# Schematic_ACSI2STM_Compact_EasyEda.net
KiCad netlist of a schematic drawn in EasyEDA
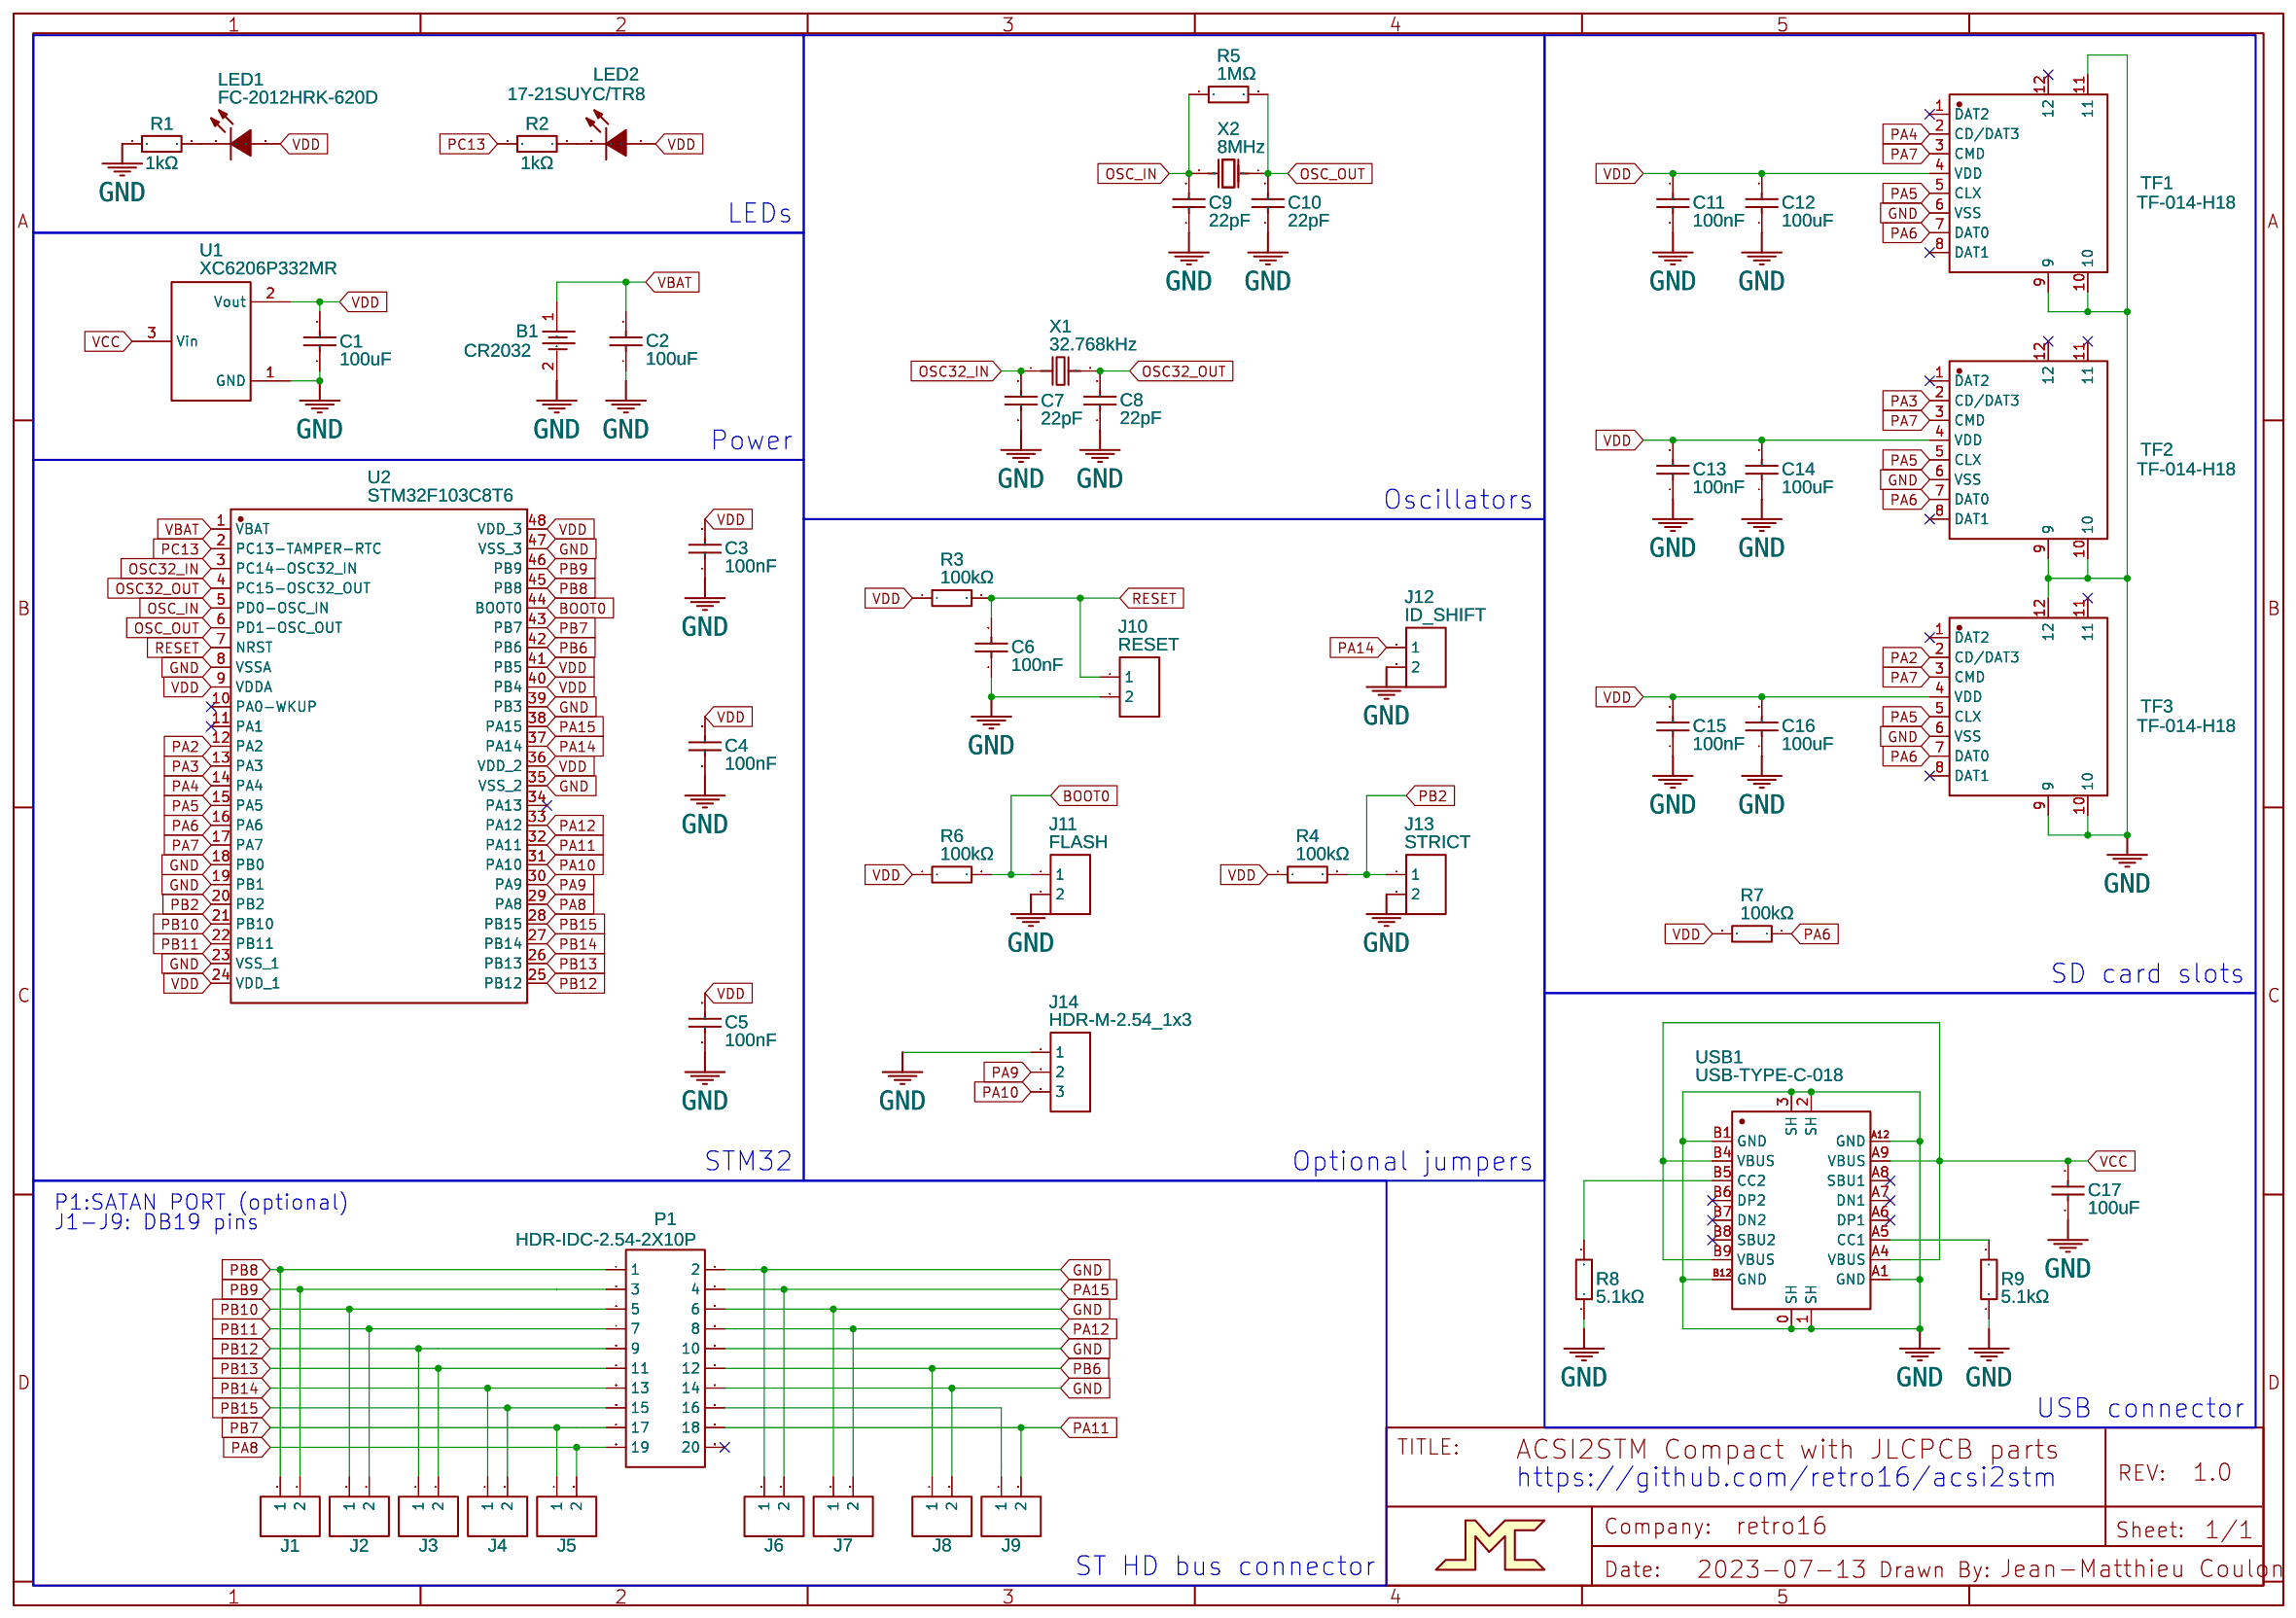
[diagram p0: schematic sheet]

(export (version "E")
  (design (tool "Eeschema 10.0.6"))
  (components
    (comp (ref "B1")
      (value "CR2032")
      (fields
        (field (name "BOM_Manufacturer Part") "CR2032-BS-6-1")
        (field (name "BOM_Supplier Part") "C70377")
      )
      (libsource (lib "") (part "CR2032-BS-6-1"))
    )
    (comp (ref "C1")
      (value "100uF")
      (fields
        (field (name "BOM_Manufacturer Part") "CL31A107MQHNNNE")
        (field (name "BOM_Supplier Part") "C15008")
      )
      (libsource (lib "") (part "CL31A107MQHNNNE"))
    )
    (comp (ref "C2")
      (value "100uF")
      (fields
        (field (name "BOM_Manufacturer Part") "CL31A107MQHNNNE")
        (field (name "BOM_Supplier Part") "C15008")
      )
      (libsource (lib "") (part "CL31A107MQHNNNE"))
    )
    (comp (ref "C3")
      (value "100nF")
      (fields
        (field (name "BOM_Manufacturer Part") "CL05B104KO5NNNC")
        (field (name "BOM_Supplier Part") "C1525")
      )
      (libsource (lib "") (part "CL05B104KO5NNNC"))
    )
    (comp (ref "C4")
      (value "100nF")
      (fields
        (field (name "BOM_Manufacturer Part") "CL05B104KO5NNNC")
        (field (name "BOM_Supplier Part") "C1525")
      )
      (libsource (lib "") (part "CL05B104KO5NNNC"))
    )
    (comp (ref "C5")
      (value "100nF")
      (fields
        (field (name "BOM_Manufacturer Part") "CL05B104KO5NNNC")
        (field (name "BOM_Supplier Part") "C1525")
      )
      (libsource (lib "") (part "CL05B104KO5NNNC"))
    )
    (comp (ref "C6")
      (value "100nF")
      (fields
        (field (name "BOM_Manufacturer Part") "CL05B104KO5NNNC")
        (field (name "BOM_Supplier Part") "C1525")
      )
      (libsource (lib "") (part "CL05B104KO5NNNC"))
    )
    (comp (ref "C7")
      (value "22pF")
      (fields
        (field (name "BOM_Manufacturer Part") "0402CG220J500NT")
        (field (name "BOM_Supplier Part") "C1555")
      )
      (libsource (lib "") (part "0402CG220J500NT"))
    )
    (comp (ref "C8")
      (value "22pF")
      (fields
        (field (name "BOM_Manufacturer Part") "0402CG220J500NT")
        (field (name "BOM_Supplier Part") "C1555")
      )
      (libsource (lib "") (part "0402CG220J500NT"))
    )
    (comp (ref "C9")
      (value "22pF")
      (fields
        (field (name "BOM_Manufacturer Part") "0402CG220J500NT")
        (field (name "BOM_Supplier Part") "C1555")
      )
      (libsource (lib "") (part "0402CG220J500NT"))
    )
    (comp (ref "C10")
      (value "22pF")
      (fields
        (field (name "BOM_Manufacturer Part") "0402CG220J500NT")
        (field (name "BOM_Supplier Part") "C1555")
      )
      (libsource (lib "") (part "0402CG220J500NT"))
    )
    (comp (ref "C11")
      (value "100nF")
      (fields
        (field (name "BOM_Manufacturer Part") "CL05B104KO5NNNC")
        (field (name "BOM_Supplier Part") "C1525")
      )
      (libsource (lib "") (part "CL05B104KO5NNNC"))
    )
    (comp (ref "C12")
      (value "100uF")
      (fields
        (field (name "BOM_Manufacturer Part") "CL31A107MQHNNNE")
        (field (name "BOM_Supplier Part") "C15008")
      )
      (libsource (lib "") (part "CL31A107MQHNNNE"))
    )
    (comp (ref "C13")
      (value "100nF")
      (fields
        (field (name "BOM_Manufacturer Part") "CL05B104KO5NNNC")
        (field (name "BOM_Supplier Part") "C1525")
      )
      (libsource (lib "") (part "CL05B104KO5NNNC"))
    )
    (comp (ref "C14")
      (value "100uF")
      (fields
        (field (name "BOM_Manufacturer Part") "CL31A107MQHNNNE")
        (field (name "BOM_Supplier Part") "C15008")
      )
      (libsource (lib "") (part "CL31A107MQHNNNE"))
    )
    (comp (ref "C15")
      (value "100nF")
      (fields
        (field (name "BOM_Manufacturer Part") "CL05B104KO5NNNC")
        (field (name "BOM_Supplier Part") "C1525")
      )
      (libsource (lib "") (part "CL05B104KO5NNNC"))
    )
    (comp (ref "C16")
      (value "100uF")
      (fields
        (field (name "BOM_Manufacturer Part") "CL31A107MQHNNNE")
        (field (name "BOM_Supplier Part") "C15008")
      )
      (libsource (lib "") (part "CL31A107MQHNNNE"))
    )
    (comp (ref "C17")
      (value "100uF")
      (fields
        (field (name "BOM_Manufacturer Part") "CL31A107MQHNNNE")
        (field (name "BOM_Supplier Part") "C15008")
      )
      (libsource (lib "") (part "CL31A107MQHNNNE"))
    )
    (comp (ref "J1")
      (value "HDR-M-2.54_1x2")
      (fields (field (name "BOM_Supplier Part") "C124375"))
      (libsource (lib "") (part "HDR-M-2.54_1x2"))
    )
    (comp (ref "J2")
      (value "HDR-M-2.54_1x2")
      (fields (field (name "BOM_Supplier Part") "C124375"))
      (libsource (lib "") (part "HDR-M-2.54_1x2"))
    )
    (comp (ref "J3")
      (value "HDR-M-2.54_1x2")
      (fields (field (name "BOM_Supplier Part") "C124375"))
      (libsource (lib "") (part "HDR-M-2.54_1x2"))
    )
    (comp (ref "J4")
      (value "HDR-M-2.54_1x2")
      (fields (field (name "BOM_Supplier Part") "C124375"))
      (libsource (lib "") (part "HDR-M-2.54_1x2"))
    )
    (comp (ref "J5")
      (value "HDR-M-2.54_1x2")
      (fields (field (name "BOM_Supplier Part") "C124375"))
      (libsource (lib "") (part "HDR-M-2.54_1x2"))
    )
    (comp (ref "J6")
      (value "HDR-M-2.54_1x2")
      (fields (field (name "BOM_Supplier Part") "C124375"))
      (libsource (lib "") (part "HDR-M-2.54_1x2"))
    )
    (comp (ref "J7")
      (value "HDR-M-2.54_1x2")
      (fields (field (name "BOM_Supplier Part") "C124375"))
      (libsource (lib "") (part "HDR-M-2.54_1x2"))
    )
    (comp (ref "J8")
      (value "HDR-M-2.54_1x2")
      (fields (field (name "BOM_Supplier Part") "C124375"))
      (libsource (lib "") (part "HDR-M-2.54_1x2"))
    )
    (comp (ref "J9")
      (value "HDR-M-2.54_1x2")
      (fields (field (name "BOM_Supplier Part") "C124375"))
      (libsource (lib "") (part "HDR-M-2.54_1x2"))
    )
    (comp (ref "J10")
      (value "RESET")
      (fields (field (name "BOM_Supplier Part") "C124375"))
      (libsource (lib "") (part "HDR-M-2.54_1x2_1"))
    )
    (comp (ref "J11")
      (value "FLASH")
      (fields (field (name "BOM_Supplier Part") "C124375"))
      (libsource (lib "") (part "HDR-M-2.54_1x2_1"))
    )
    (comp (ref "J12")
      (value "ID_SHIFT")
      (fields (field (name "BOM_Supplier Part") "C124375"))
      (libsource (lib "") (part "HDR-M-2.54_1x2_1"))
    )
    (comp (ref "J13")
      (value "STRICT")
      (fields (field (name "BOM_Supplier Part") "C124375"))
      (libsource (lib "") (part "HDR-M-2.54_1x2_1"))
    )
    (comp (ref "J14")
      (value "HDR-M-2.54_1x3")
      (fields (field (name "BOM_Supplier Part") "C180248"))
      (libsource (lib "") (part "HDR-M-2.54_1x3"))
    )
    (comp (ref "LED1")
      (value "FC-2012HRK-620D")
      (fields (field (name "BOM_Manufacturer Part") "NCD0805R1") (field (name "BOM_Supplier Part") "C84256"))
      (libsource (lib "") (part "FC-2012HRK-620D"))
    )
    (comp (ref "LED2")
      (value "17-21SUYC/TR8")
      (fields (field (name "BOM_Manufacturer Part") "KT-0805黄灯") (field (name "BOM_Supplier Part") "C2296"))
      (libsource (lib "") (part "17-21SUYC/TR8"))
    )
    (comp (ref "P1")
      (value "HDR-IDC-2.54-2X10P")
      (fields
        (field (name "BOM_Manufacturer Part") "IDC Box 2.54mm 2X10P　Straight")
        (field (name "BOM_Supplier Part") "C3405")
      )
      (libsource (lib "") (part "HDR-IDC-2.54-2X10P"))
    )
    (comp (ref "R1")
      (value "1kΩ")
      (fields
        (field (name "BOM_Manufacturer Part") "0402WGF1001TCE")
        (field (name "BOM_Supplier Part") "C11702")
      )
      (libsource (lib "") (part "0402WGF1001TCE"))
    )
    (comp (ref "R2")
      (value "1kΩ")
      (fields
        (field (name "BOM_Manufacturer Part") "0402WGF1001TCE")
        (field (name "BOM_Supplier Part") "C11702")
      )
      (libsource (lib "") (part "0402WGF1001TCE"))
    )
    (comp (ref "R3")
      (value "100kΩ")
      (fields
        (field (name "BOM_Manufacturer Part") "0402WGF1003TCE")
        (field (name "BOM_Supplier Part") "C25741")
      )
      (libsource (lib "") (part "0402WGF1003TCE"))
    )
    (comp (ref "R4")
      (value "100kΩ")
      (fields
        (field (name "BOM_Manufacturer Part") "0402WGF1003TCE")
        (field (name "BOM_Supplier Part") "C25741")
      )
      (libsource (lib "") (part "0402WGF1003TCE"))
    )
    (comp (ref "R5")
      (value "1MΩ")
      (fields
        (field (name "BOM_Manufacturer Part") "0402WGF1004TCE")
        (field (name "BOM_Supplier Part") "C26083")
      )
      (libsource (lib "") (part "0402WGF1004TCE"))
    )
    (comp (ref "R6")
      (value "100kΩ")
      (fields
        (field (name "BOM_Manufacturer Part") "0402WGF1003TCE")
        (field (name "BOM_Supplier Part") "C25741")
      )
      (libsource (lib "") (part "0402WGF1003TCE"))
    )
    (comp (ref "R7")
      (value "100kΩ")
      (fields
        (field (name "BOM_Manufacturer Part") "0402WGF1003TCE")
        (field (name "BOM_Supplier Part") "C25741")
      )
      (libsource (lib "") (part "0402WGF1003TCE_1"))
    )
    (comp (ref "R8")
      (value "5.1kΩ")
      (fields
        (field (name "BOM_Manufacturer Part") "0402WGF5101TCE")
        (field (name "BOM_Supplier Part") "C25905")
      )
      (libsource (lib "") (part "0402WGF5101TCE"))
    )
    (comp (ref "R9")
      (value "5.1kΩ")
      (fields
        (field (name "BOM_Manufacturer Part") "0402WGF5101TCE")
        (field (name "BOM_Supplier Part") "C25905")
      )
      (libsource (lib "") (part "0402WGF5101TCE"))
    )
    (comp (ref "TF1")
      (value "TF-014-H18")
      (fields (field (name "BOM_Supplier Part") "C410349"))
      (libsource (lib "") (part "TF-014-H18"))
    )
    (comp (ref "TF2")
      (value "TF-014-H18")
      (fields (field (name "BOM_Supplier Part") "C410349"))
      (libsource (lib "") (part "TF-014-H18"))
    )
    (comp (ref "TF3")
      (value "TF-014-H18")
      (fields (field (name "BOM_Supplier Part") "C410349"))
      (libsource (lib "") (part "TF-014-H18"))
    )
    (comp (ref "U1")
      (value "XC6206P332MR")
      (fields (field (name "BOM_Supplier Part") "C5446"))
      (libsource (lib "") (part "XC6206P332MR"))
    )
    (comp (ref "U2")
      (value "STM32F103C8T6")
      (fields (field (name "BOM_Supplier Part") "C8734"))
      (libsource (lib "") (part "STM32F103C8T6"))
    )
    (comp (ref "U3") (value "JMC_LOGO") (libsource (lib "") (part "JMC_LOGO")))
    (comp (ref "USB1")
      (value "USB-TYPE-C-018")
      (fields (field (name "BOM_Supplier Part") "C2927038"))
      (libsource (lib "") (part "USB-TYPE-C-018"))
    )
    (comp (ref "X1")
      (value "32.768kHz")
      (fields
        (field (name "BOM_Manufacturer Part") "Q13FC1350000400")
        (field (name "BOM_Supplier Part") "C32346")
      )
      (libsource (lib "") (part "Q13FC1350000400"))
    )
    (comp (ref "X2")
      (value "8MHz")
      (fields
        (field (name "BOM_Manufacturer Part") "X49SM8MSD2SC")
        (field (name "BOM_Supplier Part") "C12674")
      )
      (libsource (lib "") (part "X49SM8MSD2SC"))
    )
  )
  (nets
    (net (code "1") (name "BOOT0") (class "Default")
      (node (ref "J11") (pin "1") (pinfunction "1_1") (pintype "unspecified"))
      (node (ref "R6") (pin "2") (pinfunction "2_2") (pintype "input"))
      (node (ref "U2") (pin "44") (pinfunction "BOOT0_44") (pintype "unspecified"))
    )
    (net (code "2") (name "GND") (class "Default")
      (node (ref "B1") (pin "2") (pinfunction "2_2") (pintype "input"))
      (node (ref "C1") (pin "1") (pinfunction "1_1") (pintype "input"))
      (node (ref "C10") (pin "1") (pinfunction "1_1") (pintype "input"))
      (node (ref "C11") (pin "1") (pinfunction "1_1") (pintype "input"))
      (node (ref "C12") (pin "1") (pinfunction "1_1") (pintype "input"))
      (node (ref "C13") (pin "1") (pinfunction "1_1") (pintype "input"))
      (node (ref "C14") (pin "1") (pinfunction "1_1") (pintype "input"))
      (node (ref "C15") (pin "1") (pinfunction "1_1") (pintype "input"))
      (node (ref "C16") (pin "1") (pinfunction "1_1") (pintype "input"))
      (node (ref "C17") (pin "1") (pinfunction "1_1") (pintype "input"))
      (node (ref "C2") (pin "1") (pinfunction "1_1") (pintype "input"))
      (node (ref "C3") (pin "1") (pinfunction "1_1") (pintype "input"))
      (node (ref "C4") (pin "1") (pinfunction "1_1") (pintype "input"))
      (node (ref "C5") (pin "1") (pinfunction "1_1") (pintype "input"))
      (node (ref "C6") (pin "1") (pinfunction "1_1") (pintype "input"))
      (node (ref "C7") (pin "1") (pinfunction "1_1") (pintype "input"))
      (node (ref "C8") (pin "1") (pinfunction "1_1") (pintype "input"))
      (node (ref "C9") (pin "1") (pinfunction "1_1") (pintype "input"))
      (node (ref "J10") (pin "2") (pinfunction "2_2") (pintype "unspecified"))
      (node (ref "J11") (pin "2") (pinfunction "2_2") (pintype "unspecified"))
      (node (ref "J12") (pin "2") (pinfunction "2_2") (pintype "unspecified"))
      (node (ref "J13") (pin "2") (pinfunction "2_2") (pintype "unspecified"))
      (node (ref "J14") (pin "1") (pinfunction "1_1") (pintype "input"))
      (node (ref "J6") (pin "1") (pinfunction "1_1") (pintype "unspecified"))
      (node (ref "J7") (pin "1") (pinfunction "1_1") (pintype "unspecified"))
      (node (ref "J8") (pin "2") (pinfunction "2_2") (pintype "unspecified"))
      (node (ref "P1") (pin "10") (pinfunction "10_10") (pintype "unspecified"))
      (node (ref "P1") (pin "14") (pinfunction "14_14") (pintype "unspecified"))
      (node (ref "P1") (pin "2") (pinfunction "2_2") (pintype "unspecified"))
      (node (ref "P1") (pin "6") (pinfunction "6_6") (pintype "unspecified"))
      (node (ref "R1") (pin "1") (pinfunction "1_1") (pintype "input"))
      (node (ref "R8") (pin "1") (pinfunction "1_1") (pintype "input"))
      (node (ref "R9") (pin "1") (pinfunction "1_1") (pintype "input"))
      (node (ref "TF1") (pin "10") (pinfunction "10_10") (pintype "unspecified"))
      (node (ref "TF1") (pin "11") (pinfunction "11_11") (pintype "unspecified"))
      (node (ref "TF1") (pin "6") (pinfunction "VSS_6") (pintype "unspecified"))
      (node (ref "TF1") (pin "9") (pinfunction "9_9") (pintype "unspecified"))
      (node (ref "TF2") (pin "10") (pinfunction "10_10") (pintype "unspecified"))
      (node (ref "TF2") (pin "6") (pinfunction "VSS_6") (pintype "unspecified"))
      (node (ref "TF2") (pin "9") (pinfunction "9_9") (pintype "unspecified"))
      (node (ref "TF3") (pin "10") (pinfunction "10_10") (pintype "unspecified"))
      (node (ref "TF3") (pin "12") (pinfunction "12_12") (pintype "unspecified"))
      (node (ref "TF3") (pin "6") (pinfunction "VSS_6") (pintype "unspecified"))
      (node (ref "TF3") (pin "9") (pinfunction "9_9") (pintype "unspecified"))
      (node (ref "U1") (pin "1") (pinfunction "GND_1") (pintype "unspecified"))
      (node (ref "U2") (pin "18") (pinfunction "PB0_18") (pintype "unspecified"))
      (node (ref "U2") (pin "19") (pinfunction "PB1_19") (pintype "unspecified"))
      (node (ref "U2") (pin "23") (pinfunction "VSS_1_23") (pintype "unspecified"))
      (node (ref "U2") (pin "35") (pinfunction "VSS_2_35") (pintype "unspecified"))
      (node (ref "U2") (pin "39") (pinfunction "PB3_39") (pintype "unspecified"))
      (node (ref "U2") (pin "47") (pinfunction "VSS_3_47") (pintype "unspecified"))
      (node (ref "U2") (pin "8") (pinfunction "VSSA_8") (pintype "unspecified"))
      (node (ref "USB1") (pin "0") (pinfunction "SH_0") (pintype "unspecified"))
      (node (ref "USB1") (pin "1") (pinfunction "SH_1") (pintype "unspecified"))
      (node (ref "USB1") (pin "2") (pinfunction "SH_2") (pintype "unspecified"))
      (node (ref "USB1") (pin "3") (pinfunction "SH_3") (pintype "unspecified"))
      (node (ref "USB1") (pin "A1") (pinfunction "GND_A1") (pintype "unspecified"))
      (node (ref "USB1") (pin "A12") (pinfunction "GND_A12") (pintype "unspecified"))
      (node (ref "USB1") (pin "B1") (pinfunction "GND_B1") (pintype "unspecified"))
      (node (ref "USB1") (pin "B12") (pinfunction "GND_B12") (pintype "unspecified"))
    )
    (net (code "3") (name "Net-(J9-Pad1)") (class "Default")
      (node (ref "J9") (pin "1") (pinfunction "1_1") (pintype "unspecified"))
      (node (ref "P1") (pin "16") (pinfunction "16_16") (pintype "unspecified"))
    )
    (net (code "4") (name "Net-(LED1--)") (class "Default")
      (node (ref "LED1") (pin "1") (pinfunction "-_1") (pintype "unspecified"))
      (node (ref "R1") (pin "2") (pinfunction "2_2") (pintype "input"))
    )
    (net (code "5") (name "Net-(LED2--)") (class "Default")
      (node (ref "LED2") (pin "2") (pinfunction "-_2") (pintype "unspecified"))
      (node (ref "R2") (pin "2") (pinfunction "2_2") (pintype "input"))
    )
    (net (code "6") (name "Net-(USB1-CC1)") (class "Default")
      (node (ref "R9") (pin "2") (pinfunction "2_2") (pintype "input"))
      (node (ref "USB1") (pin "A5") (pinfunction "CC1_A5") (pintype "unspecified"))
    )
    (net (code "7") (name "Net-(USB1-CC2)") (class "Default")
      (node (ref "R8") (pin "2") (pinfunction "2_2") (pintype "input"))
      (node (ref "USB1") (pin "B5") (pinfunction "CC2_B5") (pintype "unspecified"))
    )
    (net (code "8") (name "OSC32_IN") (class "Default")
      (node (ref "C7") (pin "2") (pinfunction "2_2") (pintype "input"))
      (node (ref "U2") (pin "3") (pinfunction "PC14-OSC32_IN_3") (pintype "unspecified"))
      (node (ref "X1") (pin "1") (pinfunction "1_1") (pintype "unspecified"))
    )
    (net (code "9") (name "OSC32_OUT") (class "Default")
      (node (ref "C8") (pin "2") (pinfunction "2_2") (pintype "input"))
      (node (ref "U2") (pin "4") (pinfunction "PC15-OSC32_OUT_4") (pintype "unspecified"))
      (node (ref "X1") (pin "2") (pinfunction "2_2") (pintype "unspecified"))
    )
    (net (code "10") (name "OSC_IN") (class "Default")
      (node (ref "C9") (pin "2") (pinfunction "2_2") (pintype "input"))
      (node (ref "R5") (pin "1") (pinfunction "1_1") (pintype "input"))
      (node (ref "U2") (pin "5") (pinfunction "PD0-OSC_IN_5") (pintype "unspecified"))
      (node (ref "X2") (pin "2") (pinfunction "OSC2_2") (pintype "input"))
    )
    (net (code "11") (name "OSC_OUT") (class "Default")
      (node (ref "C10") (pin "2") (pinfunction "2_2") (pintype "input"))
      (node (ref "R5") (pin "2") (pinfunction "2_2") (pintype "input"))
      (node (ref "U2") (pin "6") (pinfunction "PD1-OSC_OUT_6") (pintype "unspecified"))
      (node (ref "X2") (pin "1") (pinfunction "OSC1_1") (pintype "input"))
    )
    (net (code "12") (name "PA2") (class "Default")
      (node (ref "TF3") (pin "2") (pinfunction "CD/DAT3_2") (pintype "unspecified"))
      (node (ref "U2") (pin "12") (pinfunction "PA2_12") (pintype "unspecified"))
    )
    (net (code "13") (name "PA3") (class "Default")
      (node (ref "TF2") (pin "2") (pinfunction "CD/DAT3_2") (pintype "unspecified"))
      (node (ref "U2") (pin "13") (pinfunction "PA3_13") (pintype "unspecified"))
    )
    (net (code "14") (name "PA4") (class "Default")
      (node (ref "TF1") (pin "2") (pinfunction "CD/DAT3_2") (pintype "unspecified"))
      (node (ref "U2") (pin "14") (pinfunction "PA4_14") (pintype "unspecified"))
    )
    (net (code "15") (name "PA5") (class "Default")
      (node (ref "TF1") (pin "5") (pinfunction "CLX_5") (pintype "unspecified"))
      (node (ref "TF2") (pin "5") (pinfunction "CLX_5") (pintype "unspecified"))
      (node (ref "TF3") (pin "5") (pinfunction "CLX_5") (pintype "unspecified"))
      (node (ref "U2") (pin "15") (pinfunction "PA5_15") (pintype "unspecified"))
    )
    (net (code "16") (name "PA6") (class "Default")
      (node (ref "R7") (pin "1") (pinfunction "1_1") (pintype "input"))
      (node (ref "TF1") (pin "7") (pinfunction "DAT0_7") (pintype "unspecified"))
      (node (ref "TF2") (pin "7") (pinfunction "DAT0_7") (pintype "unspecified"))
      (node (ref "TF3") (pin "7") (pinfunction "DAT0_7") (pintype "unspecified"))
      (node (ref "U2") (pin "16") (pinfunction "PA6_16") (pintype "unspecified"))
    )
    (net (code "17") (name "PA7") (class "Default")
      (node (ref "TF1") (pin "3") (pinfunction "CMD_3") (pintype "unspecified"))
      (node (ref "TF2") (pin "3") (pinfunction "CMD_3") (pintype "unspecified"))
      (node (ref "TF3") (pin "3") (pinfunction "CMD_3") (pintype "unspecified"))
      (node (ref "U2") (pin "17") (pinfunction "PA7_17") (pintype "unspecified"))
    )
    (net (code "18") (name "PA8") (class "Default")
      (node (ref "J5") (pin "2") (pinfunction "2_2") (pintype "unspecified"))
      (node (ref "P1") (pin "19") (pinfunction "19_19") (pintype "unspecified"))
      (node (ref "U2") (pin "29") (pinfunction "PA8_29") (pintype "unspecified"))
    )
    (net (code "19") (name "PA9") (class "Default")
      (node (ref "J14") (pin "2") (pinfunction "2_2") (pintype "input"))
      (node (ref "U2") (pin "30") (pinfunction "PA9_30") (pintype "unspecified"))
    )
    (net (code "20") (name "PA10") (class "Default")
      (node (ref "J14") (pin "3") (pinfunction "3_3") (pintype "input"))
      (node (ref "U2") (pin "31") (pinfunction "PA10_31") (pintype "unspecified"))
    )
    (net (code "21") (name "PA11") (class "Default")
      (node (ref "J9") (pin "2") (pinfunction "2_2") (pintype "unspecified"))
      (node (ref "P1") (pin "18") (pinfunction "18_18") (pintype "unspecified"))
      (node (ref "U2") (pin "32") (pinfunction "PA11_32") (pintype "unspecified"))
    )
    (net (code "22") (name "PA12") (class "Default")
      (node (ref "J7") (pin "2") (pinfunction "2_2") (pintype "unspecified"))
      (node (ref "P1") (pin "8") (pinfunction "8_8") (pintype "unspecified"))
      (node (ref "U2") (pin "33") (pinfunction "PA12_33") (pintype "unspecified"))
    )
    (net (code "23") (name "PA14") (class "Default")
      (node (ref "J12") (pin "1") (pinfunction "1_1") (pintype "unspecified"))
      (node (ref "U2") (pin "37") (pinfunction "PA14_37") (pintype "unspecified"))
    )
    (net (code "24") (name "PA15") (class "Default")
      (node (ref "J6") (pin "2") (pinfunction "2_2") (pintype "unspecified"))
      (node (ref "P1") (pin "4") (pinfunction "4_4") (pintype "unspecified"))
      (node (ref "U2") (pin "38") (pinfunction "PA15_38") (pintype "unspecified"))
    )
    (net (code "25") (name "PB2") (class "Default")
      (node (ref "J13") (pin "1") (pinfunction "1_1") (pintype "unspecified"))
      (node (ref "R4") (pin "2") (pinfunction "2_2") (pintype "input"))
      (node (ref "U2") (pin "20") (pinfunction "PB2_20") (pintype "unspecified"))
    )
    (net (code "26") (name "PB6") (class "Default")
      (node (ref "J8") (pin "1") (pinfunction "1_1") (pintype "unspecified"))
      (node (ref "P1") (pin "12") (pinfunction "12_12") (pintype "unspecified"))
      (node (ref "U2") (pin "42") (pinfunction "PB6_42") (pintype "unspecified"))
    )
    (net (code "27") (name "PB7") (class "Default")
      (node (ref "J5") (pin "1") (pinfunction "1_1") (pintype "unspecified"))
      (node (ref "P1") (pin "17") (pinfunction "17_17") (pintype "unspecified"))
      (node (ref "U2") (pin "43") (pinfunction "PB7_43") (pintype "unspecified"))
    )
    (net (code "28") (name "PB8") (class "Default")
      (node (ref "J1") (pin "1") (pinfunction "1_1") (pintype "unspecified"))
      (node (ref "P1") (pin "1") (pinfunction "1_1") (pintype "unspecified"))
      (node (ref "U2") (pin "45") (pinfunction "PB8_45") (pintype "unspecified"))
    )
    (net (code "29") (name "PB9") (class "Default")
      (node (ref "J1") (pin "2") (pinfunction "2_2") (pintype "unspecified"))
      (node (ref "P1") (pin "3") (pinfunction "3_3") (pintype "unspecified"))
      (node (ref "U2") (pin "46") (pinfunction "PB9_46") (pintype "unspecified"))
    )
    (net (code "30") (name "PB10") (class "Default")
      (node (ref "J2") (pin "1") (pinfunction "1_1") (pintype "unspecified"))
      (node (ref "P1") (pin "5") (pinfunction "5_5") (pintype "unspecified"))
      (node (ref "U2") (pin "21") (pinfunction "PB10_21") (pintype "unspecified"))
    )
    (net (code "31") (name "PB11") (class "Default")
      (node (ref "J2") (pin "2") (pinfunction "2_2") (pintype "unspecified"))
      (node (ref "P1") (pin "7") (pinfunction "7_7") (pintype "unspecified"))
      (node (ref "U2") (pin "22") (pinfunction "PB11_22") (pintype "unspecified"))
    )
    (net (code "32") (name "PB12") (class "Default")
      (node (ref "J3") (pin "1") (pinfunction "1_1") (pintype "unspecified"))
      (node (ref "P1") (pin "9") (pinfunction "9_9") (pintype "unspecified"))
      (node (ref "U2") (pin "25") (pinfunction "PB12_25") (pintype "unspecified"))
    )
    (net (code "33") (name "PB13") (class "Default")
      (node (ref "J3") (pin "2") (pinfunction "2_2") (pintype "unspecified"))
      (node (ref "P1") (pin "11") (pinfunction "11_11") (pintype "unspecified"))
      (node (ref "U2") (pin "26") (pinfunction "PB13_26") (pintype "unspecified"))
    )
    (net (code "34") (name "PB14") (class "Default")
      (node (ref "J4") (pin "1") (pinfunction "1_1") (pintype "unspecified"))
      (node (ref "P1") (pin "13") (pinfunction "13_13") (pintype "unspecified"))
      (node (ref "U2") (pin "27") (pinfunction "PB14_27") (pintype "unspecified"))
    )
    (net (code "35") (name "PB15") (class "Default")
      (node (ref "J4") (pin "2") (pinfunction "2_2") (pintype "unspecified"))
      (node (ref "P1") (pin "15") (pinfunction "15_15") (pintype "unspecified"))
      (node (ref "U2") (pin "28") (pinfunction "PB15_28") (pintype "unspecified"))
    )
    (net (code "36") (name "PC13") (class "Default")
      (node (ref "R2") (pin "1") (pinfunction "1_1") (pintype "input"))
      (node (ref "U2") (pin "2") (pinfunction "PC13-TAMPER-RTC_2") (pintype "unspecified"))
    )
    (net (code "37") (name "RESET") (class "Default")
      (node (ref "C6") (pin "2") (pinfunction "2_2") (pintype "input"))
      (node (ref "J10") (pin "1") (pinfunction "1_1") (pintype "unspecified"))
      (node (ref "R3") (pin "2") (pinfunction "2_2") (pintype "input"))
      (node (ref "U2") (pin "7") (pinfunction "NRST_7") (pintype "unspecified"))
    )
    (net (code "38") (name "VBAT") (class "Default")
      (node (ref "B1") (pin "1") (pinfunction "1_1") (pintype "input"))
      (node (ref "C2") (pin "2") (pinfunction "2_2") (pintype "input"))
      (node (ref "U2") (pin "1") (pinfunction "VBAT_1") (pintype "unspecified"))
    )
    (net (code "39") (name "VCC") (class "Default")
      (node (ref "C17") (pin "2") (pinfunction "2_2") (pintype "input"))
      (node (ref "U1") (pin "3") (pinfunction "Vin_3") (pintype "unspecified"))
      (node (ref "USB1") (pin "A4") (pinfunction "VBUS_A4") (pintype "unspecified"))
      (node (ref "USB1") (pin "A9") (pinfunction "VBUS_A9") (pintype "unspecified"))
      (node (ref "USB1") (pin "B4") (pinfunction "VBUS_B4") (pintype "unspecified"))
      (node (ref "USB1") (pin "B9") (pinfunction "VBUS_B9") (pintype "unspecified"))
    )
    (net (code "40") (name "VDD") (class "Default")
      (node (ref "C1") (pin "2") (pinfunction "2_2") (pintype "input"))
      (node (ref "C11") (pin "2") (pinfunction "2_2") (pintype "input"))
      (node (ref "C12") (pin "2") (pinfunction "2_2") (pintype "input"))
      (node (ref "C13") (pin "2") (pinfunction "2_2") (pintype "input"))
      (node (ref "C14") (pin "2") (pinfunction "2_2") (pintype "input"))
      (node (ref "C15") (pin "2") (pinfunction "2_2") (pintype "input"))
      (node (ref "C16") (pin "2") (pinfunction "2_2") (pintype "input"))
      (node (ref "C3") (pin "2") (pinfunction "2_2") (pintype "input"))
      (node (ref "C4") (pin "2") (pinfunction "2_2") (pintype "input"))
      (node (ref "C5") (pin "2") (pinfunction "2_2") (pintype "input"))
      (node (ref "LED1") (pin "2") (pinfunction "+_2") (pintype "unspecified"))
      (node (ref "LED2") (pin "1") (pinfunction "+_1") (pintype "unspecified"))
      (node (ref "R3") (pin "1") (pinfunction "1_1") (pintype "input"))
      (node (ref "R4") (pin "1") (pinfunction "1_1") (pintype "input"))
      (node (ref "R6") (pin "1") (pinfunction "1_1") (pintype "input"))
      (node (ref "R7") (pin "2") (pinfunction "2_2") (pintype "input"))
      (node (ref "TF1") (pin "4") (pinfunction "VDD_4") (pintype "unspecified"))
      (node (ref "TF2") (pin "4") (pinfunction "VDD_4") (pintype "unspecified"))
      (node (ref "TF3") (pin "4") (pinfunction "VDD_4") (pintype "unspecified"))
      (node (ref "U1") (pin "2") (pinfunction "Vout_2") (pintype "unspecified"))
      (node (ref "U2") (pin "24") (pinfunction "VDD_1_24") (pintype "unspecified"))
      (node (ref "U2") (pin "36") (pinfunction "VDD_2_36") (pintype "unspecified"))
      (node (ref "U2") (pin "40") (pinfunction "PB4_40") (pintype "unspecified"))
      (node (ref "U2") (pin "41") (pinfunction "PB5_41") (pintype "unspecified"))
      (node (ref "U2") (pin "48") (pinfunction "VDD_3_48") (pintype "unspecified"))
      (node (ref "U2") (pin "9") (pinfunction "VDDA_9") (pintype "unspecified"))
    )
    (net (code "41") (name "unconnected-(P1-Pad20)") (class "Default")
      (node (ref "P1") (pin "20") (pinfunction "20_20") (pintype "unspecified+no_connect"))
    )
    (net (code "42") (name "unconnected-(TF1-DAT1-Pad8)") (class "Default")
      (node (ref "TF1") (pin "8") (pinfunction "DAT1_8") (pintype "unspecified+no_connect"))
    )
    (net (code "43") (name "unconnected-(TF1-DAT2-Pad1)") (class "Default")
      (node (ref "TF1") (pin "1") (pinfunction "DAT2_1") (pintype "unspecified+no_connect"))
    )
    (net (code "44") (name "unconnected-(TF1-Pad12)") (class "Default")
      (node (ref "TF1") (pin "12") (pinfunction "12_12") (pintype "unspecified+no_connect"))
    )
    (net (code "45") (name "unconnected-(TF2-DAT1-Pad8)") (class "Default")
      (node (ref "TF2") (pin "8") (pinfunction "DAT1_8") (pintype "unspecified+no_connect"))
    )
    (net (code "46") (name "unconnected-(TF2-DAT2-Pad1)") (class "Default")
      (node (ref "TF2") (pin "1") (pinfunction "DAT2_1") (pintype "unspecified+no_connect"))
    )
    (net (code "47") (name "unconnected-(TF2-Pad11)") (class "Default")
      (node (ref "TF2") (pin "11") (pinfunction "11_11") (pintype "unspecified+no_connect"))
    )
    (net (code "48") (name "unconnected-(TF2-Pad12)") (class "Default")
      (node (ref "TF2") (pin "12") (pinfunction "12_12") (pintype "unspecified+no_connect"))
    )
    (net (code "49") (name "unconnected-(TF3-DAT1-Pad8)") (class "Default")
      (node (ref "TF3") (pin "8") (pinfunction "DAT1_8") (pintype "unspecified+no_connect"))
    )
    (net (code "50") (name "unconnected-(TF3-DAT2-Pad1)") (class "Default")
      (node (ref "TF3") (pin "1") (pinfunction "DAT2_1") (pintype "unspecified+no_connect"))
    )
    (net (code "51") (name "unconnected-(TF3-Pad11)") (class "Default")
      (node (ref "TF3") (pin "11") (pinfunction "11_11") (pintype "unspecified+no_connect"))
    )
    (net (code "52") (name "unconnected-(U2-PA0-WKUP-Pad10)") (class "Default")
      (node (ref "U2") (pin "10") (pinfunction "PA0-WKUP_10") (pintype "unspecified+no_connect"))
    )
    (net (code "53") (name "unconnected-(U2-PA1-Pad11)") (class "Default")
      (node (ref "U2") (pin "11") (pinfunction "PA1_11") (pintype "unspecified+no_connect"))
    )
    (net (code "54") (name "unconnected-(U2-PA13-Pad34)") (class "Default")
      (node (ref "U2") (pin "34") (pinfunction "PA13_34") (pintype "unspecified+no_connect"))
    )
    (net (code "55") (name "unconnected-(USB1-DN1-PadA7)") (class "Default")
      (node (ref "USB1") (pin "A7") (pinfunction "DN1_A7") (pintype "unspecified+no_connect"))
    )
    (net (code "56") (name "unconnected-(USB1-DN2-PadB7)") (class "Default")
      (node (ref "USB1") (pin "B7") (pinfunction "DN2_B7") (pintype "unspecified+no_connect"))
    )
    (net (code "57") (name "unconnected-(USB1-DP1-PadA6)") (class "Default")
      (node (ref "USB1") (pin "A6") (pinfunction "DP1_A6") (pintype "unspecified+no_connect"))
    )
    (net (code "58") (name "unconnected-(USB1-DP2-PadB6)") (class "Default")
      (node (ref "USB1") (pin "B6") (pinfunction "DP2_B6") (pintype "unspecified+no_connect"))
    )
    (net (code "59") (name "unconnected-(USB1-SBU1-PadA8)") (class "Default")
      (node (ref "USB1") (pin "A8") (pinfunction "SBU1_A8") (pintype "unspecified+no_connect"))
    )
    (net (code "60") (name "unconnected-(USB1-SBU2-PadB8)") (class "Default")
      (node (ref "USB1") (pin "B8") (pinfunction "SBU2_B8") (pintype "unspecified+no_connect"))
    )
  )
)
